# Eddy_Backplane.net
KiCad netlist of a schematic drawn in EAGLE
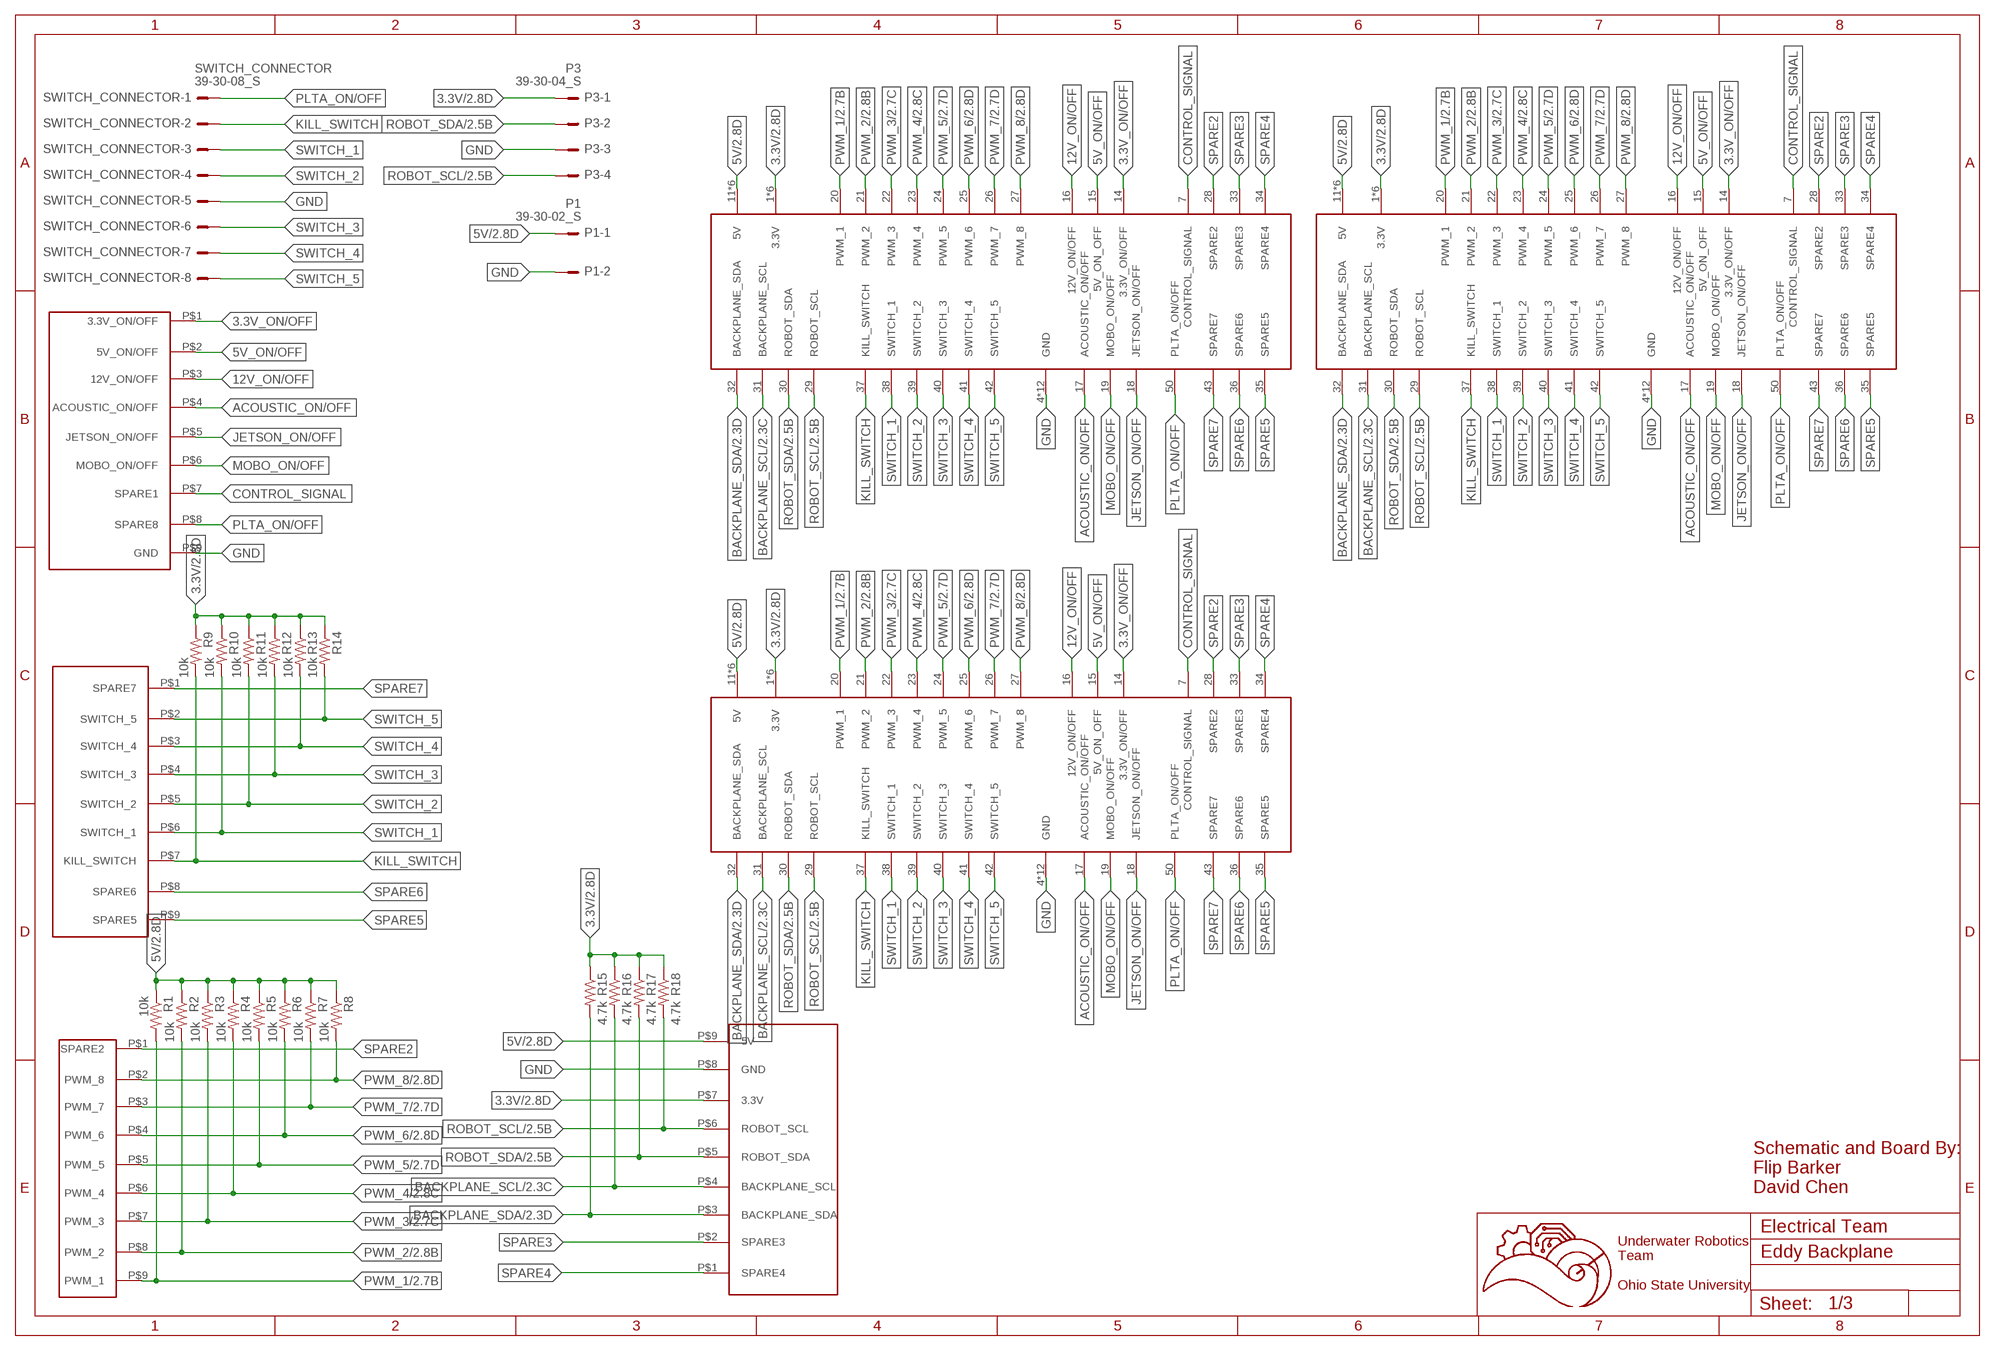
[diagram p0: schematic, sheet 1]
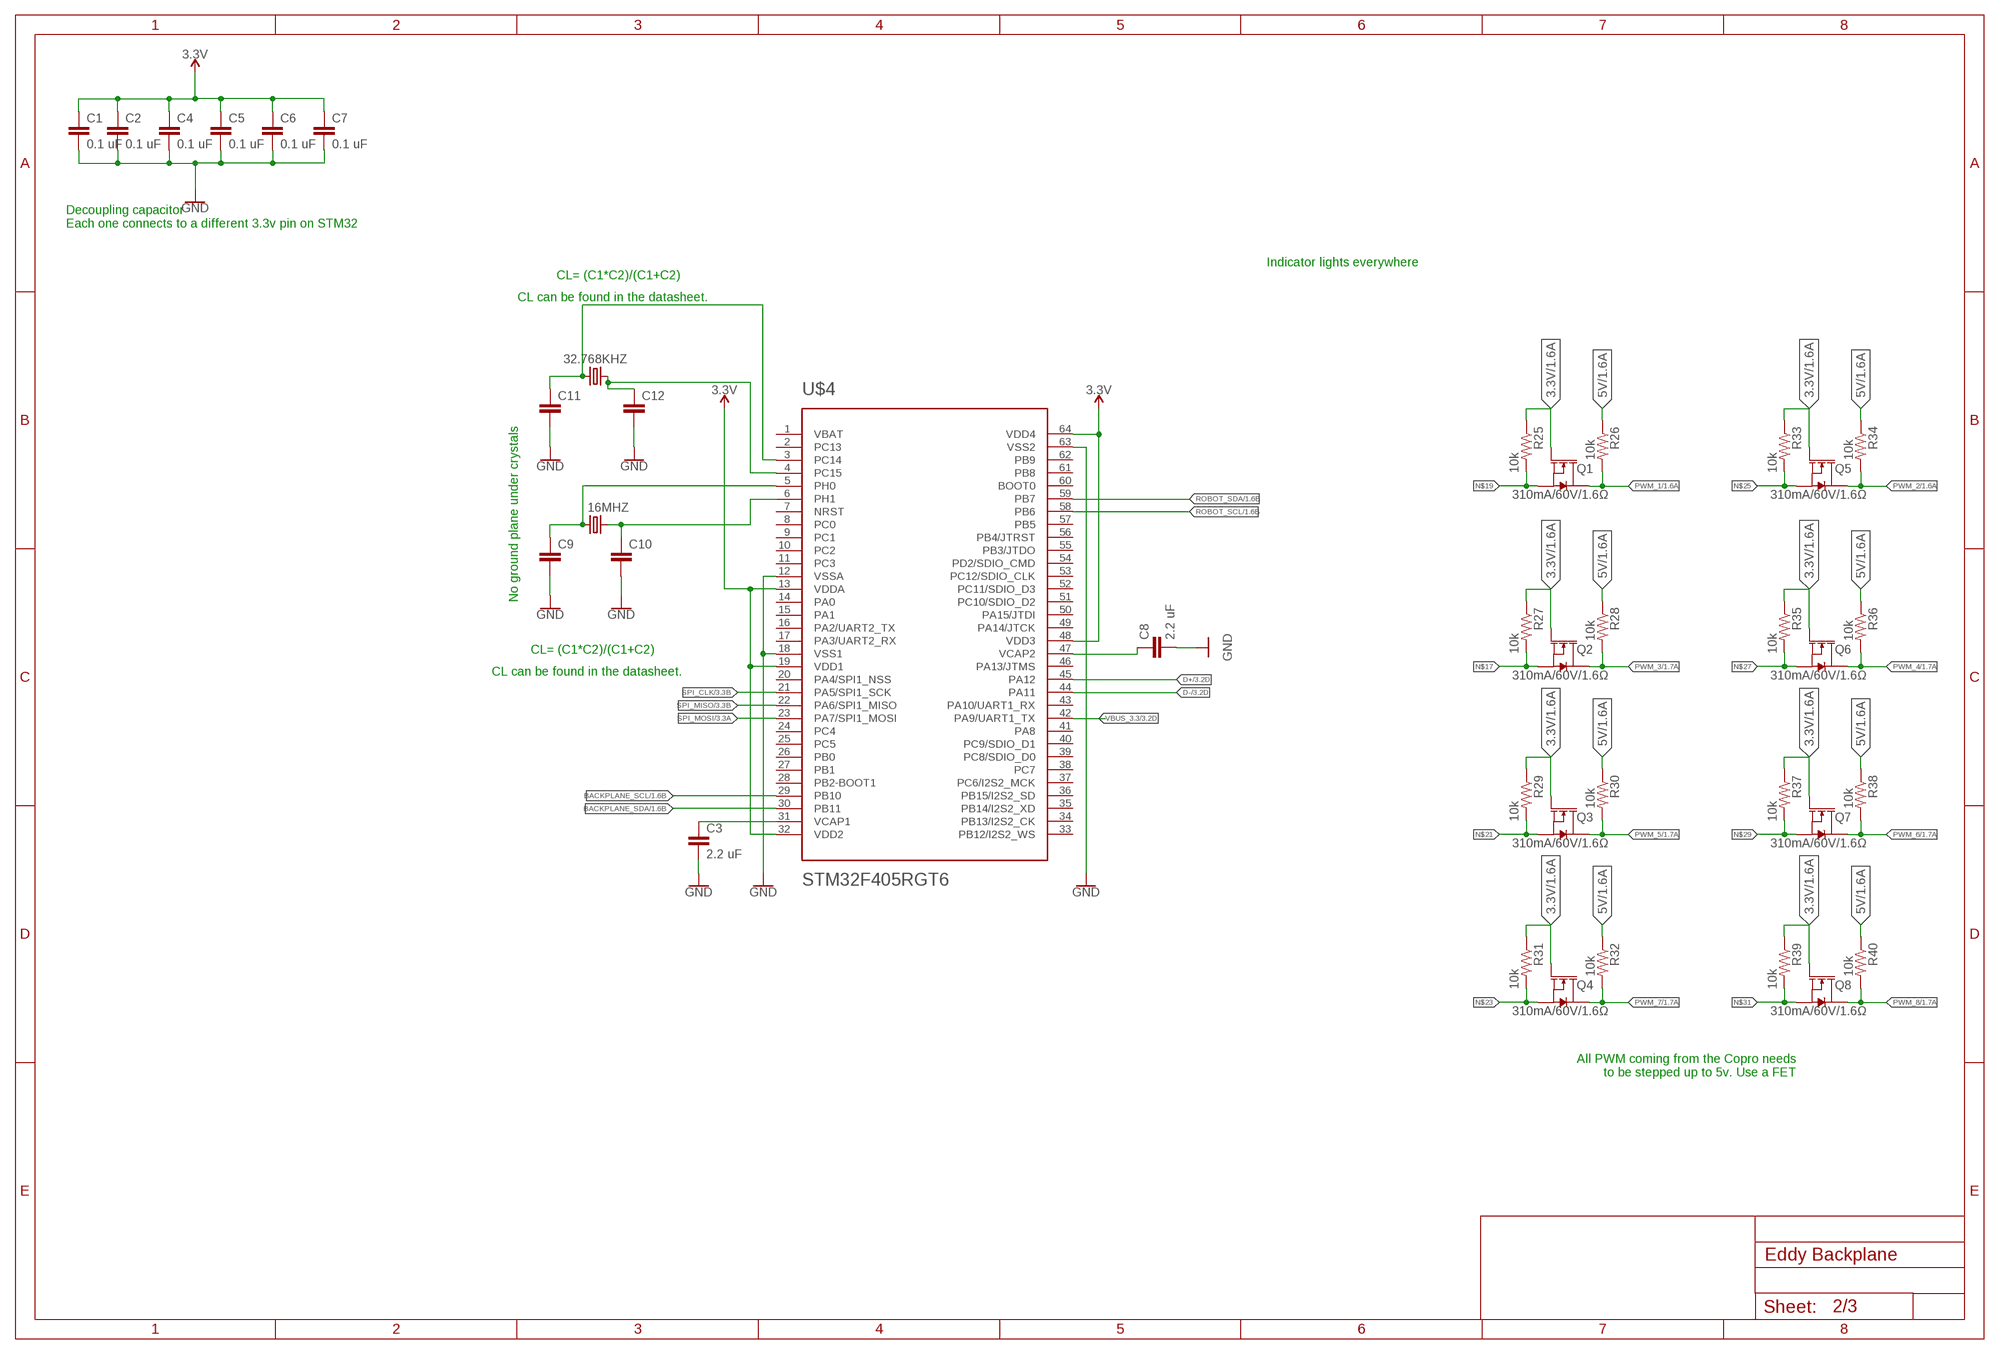
[diagram p1: schematic, sheet 2]
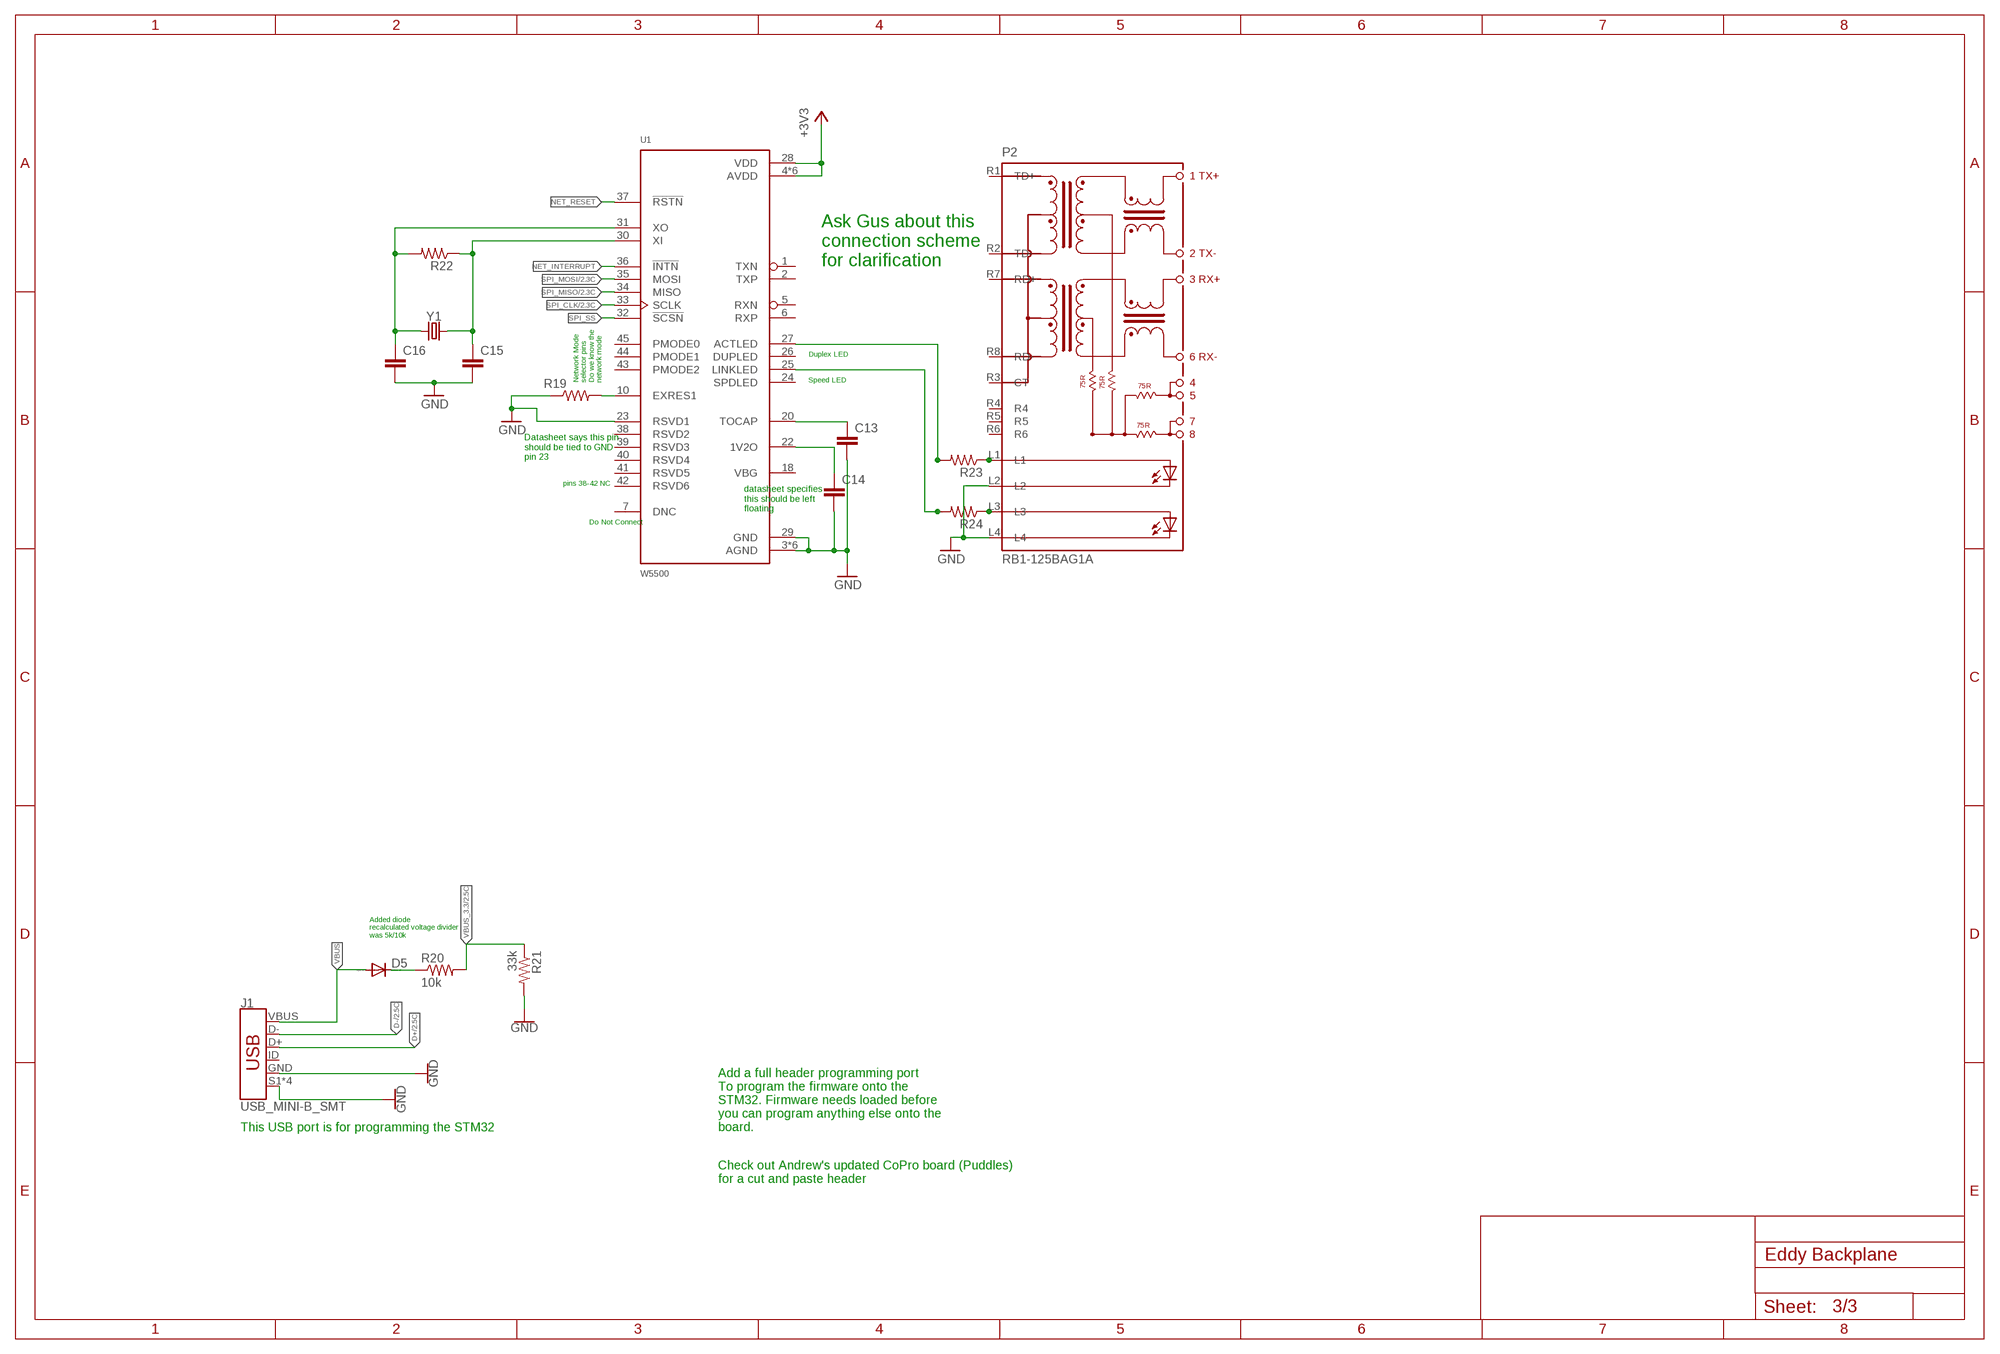
[diagram p2: schematic, sheet 3]

(export (version "E")
  (design (tool "Eeschema 10.0.6"))
  (components
    (comp (ref "C13")
      (value "C-EUC0603")
      (footprint "eagle-import:C0603")
      (libsource (lib "eagle-import") (part "C-EUC0603"))
    )
    (comp (ref "C14")
      (value "C-EUC0603")
      (footprint "eagle-import:C0603")
      (libsource (lib "eagle-import") (part "C-EUC0603"))
    )
    (comp (ref "C15")
      (value "C-EUC0603")
      (footprint "eagle-import:C0603")
      (libsource (lib "eagle-import") (part "C-EUC0603"))
    )
    (comp (ref "C16")
      (value "C-EUC0603")
      (footprint "eagle-import:C0603")
      (libsource (lib "eagle-import") (part "C-EUC0603"))
    )
    (comp (ref "D5")
      (value "DIODE-SMB")
      (footprint "eagle-import:SMB")
      (libsource (lib "eagle-import") (part "DIODE-SMB"))
    )
    (comp (ref "J1")
      (value "USB_MINI-B_SMT")
      (footprint "eagle-import:USB-MINIB")
      (libsource (lib "eagle-import") (part "USB_MINI-B_SMT"))
    )
    (comp (ref "P2")
      (value "RB1-125BAG1A")
      (footprint "eagle-import:WIZNET_RB1-125BAG1A")
      (fields (field (name "MF") "WIZnet"))
      (libsource (lib "eagle-import") (part "RB1-125BAG1A"))
    )
    (comp (ref "R19")
      (value "R-US_R0603")
      (footprint "eagle-import:R0603")
      (libsource (lib "eagle-import") (part "R-US_R0603"))
    )
    (comp (ref "R20")
      (value "10k")
      (footprint "eagle-import:R0603")
      (libsource (lib "eagle-import") (part "R-US_R0603"))
    )
    (comp (ref "R21")
      (value "33k")
      (footprint "eagle-import:R0603")
      (libsource (lib "eagle-import") (part "R-US_R0603"))
    )
    (comp (ref "R22")
      (value "R-US_R0603")
      (footprint "eagle-import:R0603")
      (libsource (lib "eagle-import") (part "R-US_R0603"))
    )
    (comp (ref "R23")
      (value "R-US_R0603")
      (footprint "eagle-import:R0603")
      (libsource (lib "eagle-import") (part "R-US_R0603"))
    )
    (comp (ref "R24")
      (value "R-US_R0603")
      (footprint "eagle-import:R0603")
      (libsource (lib "eagle-import") (part "R-US_R0603"))
    )
    (comp (ref "U1")
      (value "W5500")
      (footprint "eagle-import:QFP50P900X900X160-48N")
      (fields (field (name "MF") "WIZnet"))
      (libsource (lib "eagle-import") (part "W5500"))
    )
    (comp (ref "Y1")
      (value "CRYSTALPTH-HC49US")
      (footprint "eagle-import:HC49US")
      (libsource (lib "eagle-import") (part "SparkFun-Clocks_511_CRYSTALPTH-HC49US"))
    )
    (comp (ref "P1")
      (value "39-30-02_S")
      (footprint "eagle-import:39-30-_02_")
      (libsource (lib "eagle-import") (part "39-30-?02?_S"))
    )
    (comp (ref "P3")
      (value "39-30-04_S")
      (footprint "eagle-import:39-30-_04_")
      (libsource (lib "eagle-import") (part "39-30-?04?_S"))
    )
    (comp (ref "PWR_ON")
      (value "929870-01-09_3")
      (footprint "eagle-import:929852-01-09_1ROW")
      (libsource (lib "eagle-import") (part "929870-01-09_3"))
    )
    (comp (ref "R1")
      (value "10k")
      (footprint "eagle-import:R0603")
      (libsource (lib "eagle-import") (part "R-US_R0603"))
    )
    (comp (ref "R2")
      (value "10k")
      (footprint "eagle-import:R0603")
      (libsource (lib "eagle-import") (part "R-US_R0603"))
    )
    (comp (ref "R3")
      (value "10k")
      (footprint "eagle-import:R0603")
      (libsource (lib "eagle-import") (part "R-US_R0603"))
    )
    (comp (ref "R4")
      (value "10k")
      (footprint "eagle-import:R0603")
      (libsource (lib "eagle-import") (part "R-US_R0603"))
    )
    (comp (ref "R5")
      (value "10k")
      (footprint "eagle-import:R0603")
      (libsource (lib "eagle-import") (part "R-US_R0603"))
    )
    (comp (ref "R6")
      (value "10k")
      (footprint "eagle-import:R0603")
      (libsource (lib "eagle-import") (part "R-US_R0603"))
    )
    (comp (ref "R7")
      (value "10k")
      (footprint "eagle-import:R0603")
      (libsource (lib "eagle-import") (part "R-US_R0603"))
    )
    (comp (ref "R8")
      (value "10k")
      (footprint "eagle-import:R0603")
      (libsource (lib "eagle-import") (part "R-US_R0603"))
    )
    (comp (ref "R9")
      (value "10k")
      (footprint "eagle-import:R0603")
      (libsource (lib "eagle-import") (part "R-US_R0603"))
    )
    (comp (ref "R10")
      (value "10k")
      (footprint "eagle-import:R0603")
      (libsource (lib "eagle-import") (part "R-US_R0603"))
    )
    (comp (ref "R11")
      (value "10k")
      (footprint "eagle-import:R0603")
      (libsource (lib "eagle-import") (part "R-US_R0603"))
    )
    (comp (ref "R12")
      (value "10k")
      (footprint "eagle-import:R0603")
      (libsource (lib "eagle-import") (part "R-US_R0603"))
    )
    (comp (ref "R13")
      (value "10k")
      (footprint "eagle-import:R0603")
      (libsource (lib "eagle-import") (part "R-US_R0603"))
    )
    (comp (ref "R14")
      (value "10k")
      (footprint "eagle-import:R0603")
      (libsource (lib "eagle-import") (part "R-US_R0603"))
    )
    (comp (ref "R15")
      (value "4.7k")
      (footprint "eagle-import:R0603")
      (libsource (lib "eagle-import") (part "R-US_R0603"))
    )
    (comp (ref "R16")
      (value "4.7k")
      (footprint "eagle-import:R0603")
      (libsource (lib "eagle-import") (part "R-US_R0603"))
    )
    (comp (ref "R17")
      (value "4.7k")
      (footprint "eagle-import:R0603")
      (libsource (lib "eagle-import") (part "R-US_R0603"))
    )
    (comp (ref "R18")
      (value "4.7k")
      (footprint "eagle-import:R0603")
      (libsource (lib "eagle-import") (part "R-US_R0603"))
    )
    (comp (ref "SWITCH_CONN")
      (value "929870-01-09_1")
      (footprint "eagle-import:929852-01-09_1ROW")
      (libsource (lib "eagle-import") (part "929870-01-09_1"))
    )
    (comp (ref "SWITCH_CONNECTOR")
      (value "39-30-08_S")
      (footprint "eagle-import:39-30-_08_")
      (libsource (lib "eagle-import") (part "39-30-?08?_S"))
    )
    (comp (ref "U$1")
      (value "5530843-FEMALE")
      (footprint "eagle-import:5530843-6-BACKPLANEMATE")
      (libsource (lib "eagle-import") (part "5530843-FEMALE"))
    )
    (comp (ref "U$2")
      (value "5530843-FEMALE")
      (footprint "eagle-import:5530843-6-BACKPLANEMATE")
      (libsource (lib "eagle-import") (part "5530843-FEMALE"))
    )
    (comp (ref "U$3")
      (value "5530843-FEMALE")
      (footprint "eagle-import:5530843-6-BACKPLANEMATE")
      (libsource (lib "eagle-import") (part "5530843-FEMALE"))
    )
    (comp (ref "U$6")
      (value "929870-01-09_2")
      (footprint "eagle-import:929852-01-09_1ROW")
      (libsource (lib "eagle-import") (part "929870-01-09_2"))
    )
    (comp (ref "U$8")
      (value "929870-01-09_4")
      (footprint "eagle-import:929852-01-09_1ROW")
      (libsource (lib "eagle-import") (part "929870-01-09_4"))
    )
    (comp (ref "16MHZ")
      (value "CRYSTALPTH-HC49US")
      (footprint "eagle-import:HC49US")
      (libsource (lib "eagle-import") (part "CRYSTALPTH-HC49US"))
    )
    (comp (ref "32.768KHZ")
      (value "CRYSTALPTH-HC49US")
      (footprint "eagle-import:HC49US")
      (libsource (lib "eagle-import") (part "CRYSTALPTH-HC49US"))
    )
    (comp (ref "C1")
      (value "0.1 uF")
      (footprint "eagle-import:C0603")
      (libsource (lib "eagle-import") (part "C-EUC0603"))
    )
    (comp (ref "C2")
      (value "0.1 uF")
      (footprint "eagle-import:C0603")
      (libsource (lib "eagle-import") (part "C-EUC0603"))
    )
    (comp (ref "C3")
      (value "2.2 uF")
      (footprint "eagle-import:C0603")
      (libsource (lib "eagle-import") (part "C-EUC0603"))
    )
    (comp (ref "C4")
      (value "0.1 uF")
      (footprint "eagle-import:C0603")
      (libsource (lib "eagle-import") (part "C-EUC0603"))
    )
    (comp (ref "C5")
      (value "0.1 uF")
      (footprint "eagle-import:C0603")
      (libsource (lib "eagle-import") (part "C-EUC0603"))
    )
    (comp (ref "C6")
      (value "0.1 uF")
      (footprint "eagle-import:C0603")
      (libsource (lib "eagle-import") (part "C-EUC0603"))
    )
    (comp (ref "C7")
      (value "0.1 uF")
      (footprint "eagle-import:C0603")
      (libsource (lib "eagle-import") (part "C-EUC0603"))
    )
    (comp (ref "C8")
      (value "2.2 uF")
      (footprint "eagle-import:C0603")
      (libsource (lib "eagle-import") (part "C-EUC0603"))
    )
    (comp (ref "C9")
      (value "C-EUC0603")
      (footprint "eagle-import:C0603")
      (libsource (lib "eagle-import") (part "C-EUC0603"))
    )
    (comp (ref "C10")
      (value "C-EUC0603")
      (footprint "eagle-import:C0603")
      (libsource (lib "eagle-import") (part "C-EUC0603"))
    )
    (comp (ref "C11")
      (value "C-EUC0603")
      (footprint "eagle-import:C0603")
      (libsource (lib "eagle-import") (part "C-EUC0603"))
    )
    (comp (ref "C12")
      (value "C-EUC0603")
      (footprint "eagle-import:C0603")
      (libsource (lib "eagle-import") (part "C-EUC0603"))
    )
    (comp (ref "Q1")
      (value "310mA/60V/1.6Ω")
      (footprint "eagle-import:SOT323")
      (libsource (lib "eagle-import") (part "MOSFET-NCH-2N7002PW"))
    )
    (comp (ref "Q2")
      (value "310mA/60V/1.6Ω")
      (footprint "eagle-import:SOT323")
      (libsource (lib "eagle-import") (part "MOSFET-NCH-2N7002PW"))
    )
    (comp (ref "Q3")
      (value "310mA/60V/1.6Ω")
      (footprint "eagle-import:SOT323")
      (libsource (lib "eagle-import") (part "MOSFET-NCH-2N7002PW"))
    )
    (comp (ref "Q4")
      (value "310mA/60V/1.6Ω")
      (footprint "eagle-import:SOT323")
      (libsource (lib "eagle-import") (part "MOSFET-NCH-2N7002PW"))
    )
    (comp (ref "Q5")
      (value "310mA/60V/1.6Ω")
      (footprint "eagle-import:SOT323")
      (libsource (lib "eagle-import") (part "MOSFET-NCH-2N7002PW"))
    )
    (comp (ref "Q6")
      (value "310mA/60V/1.6Ω")
      (footprint "eagle-import:SOT323")
      (libsource (lib "eagle-import") (part "MOSFET-NCH-2N7002PW"))
    )
    (comp (ref "Q7")
      (value "310mA/60V/1.6Ω")
      (footprint "eagle-import:SOT323")
      (libsource (lib "eagle-import") (part "MOSFET-NCH-2N7002PW"))
    )
    (comp (ref "Q8")
      (value "310mA/60V/1.6Ω")
      (footprint "eagle-import:SOT323")
      (libsource (lib "eagle-import") (part "MOSFET-NCH-2N7002PW"))
    )
    (comp (ref "R25")
      (value "10k")
      (footprint "eagle-import:R0603")
      (libsource (lib "eagle-import") (part "R-US_R0603"))
    )
    (comp (ref "R26")
      (value "10k")
      (footprint "eagle-import:R0603")
      (libsource (lib "eagle-import") (part "R-US_R0603"))
    )
    (comp (ref "R27")
      (value "10k")
      (footprint "eagle-import:R0603")
      (libsource (lib "eagle-import") (part "R-US_R0603"))
    )
    (comp (ref "R28")
      (value "10k")
      (footprint "eagle-import:R0603")
      (libsource (lib "eagle-import") (part "R-US_R0603"))
    )
    (comp (ref "R29")
      (value "10k")
      (footprint "eagle-import:R0603")
      (libsource (lib "eagle-import") (part "R-US_R0603"))
    )
    (comp (ref "R30")
      (value "10k")
      (footprint "eagle-import:R0603")
      (libsource (lib "eagle-import") (part "R-US_R0603"))
    )
    (comp (ref "R31")
      (value "10k")
      (footprint "eagle-import:R0603")
      (libsource (lib "eagle-import") (part "R-US_R0603"))
    )
    (comp (ref "R32")
      (value "10k")
      (footprint "eagle-import:R0603")
      (libsource (lib "eagle-import") (part "R-US_R0603"))
    )
    (comp (ref "R33")
      (value "10k")
      (footprint "eagle-import:R0603")
      (libsource (lib "eagle-import") (part "R-US_R0603"))
    )
    (comp (ref "R34")
      (value "10k")
      (footprint "eagle-import:R0603")
      (libsource (lib "eagle-import") (part "R-US_R0603"))
    )
    (comp (ref "R35")
      (value "10k")
      (footprint "eagle-import:R0603")
      (libsource (lib "eagle-import") (part "R-US_R0603"))
    )
    (comp (ref "R36")
      (value "10k")
      (footprint "eagle-import:R0603")
      (libsource (lib "eagle-import") (part "R-US_R0603"))
    )
    (comp (ref "R37")
      (value "10k")
      (footprint "eagle-import:R0603")
      (libsource (lib "eagle-import") (part "R-US_R0603"))
    )
    (comp (ref "R38")
      (value "10k")
      (footprint "eagle-import:R0603")
      (libsource (lib "eagle-import") (part "R-US_R0603"))
    )
    (comp (ref "R39")
      (value "10k")
      (footprint "eagle-import:R0603")
      (libsource (lib "eagle-import") (part "R-US_R0603"))
    )
    (comp (ref "R40")
      (value "10k")
      (footprint "eagle-import:R0603")
      (libsource (lib "eagle-import") (part "R-US_R0603"))
    )
    (comp (ref "U$4")
      (value "STM32F405RGT6")
      (footprint "eagle-import:TQFP64")
      (libsource (lib "eagle-import") (part "STM32F405RG"))
    )
  )
  (nets
    (net (code "1") (name "+3V3") (class "Default")
      (node (ref "U1") (pin "11") (pinfunction "AVDD_11") (pintype "power_in"))
      (node (ref "U1") (pin "15") (pinfunction "AVDD_15") (pintype "power_in"))
      (node (ref "U1") (pin "17") (pinfunction "AVDD_17") (pintype "power_in"))
      (node (ref "U1") (pin "21") (pinfunction "AVDD_21") (pintype "power_in"))
      (node (ref "U1") (pin "28") (pinfunction "VDD_28") (pintype "power_in"))
      (node (ref "U1") (pin "4") (pinfunction "AVDD_4") (pintype "power_in"))
      (node (ref "U1") (pin "8") (pinfunction "AVDD_8") (pintype "power_in"))
    )
    (net (code "2") (name "3.3V") (class "Default")
      (node (ref "C1") (pin "1") (pinfunction "1_1") (pintype "passive"))
      (node (ref "C2") (pin "1") (pinfunction "1_1") (pintype "passive"))
      (node (ref "C4") (pin "1") (pinfunction "1_1") (pintype "passive"))
      (node (ref "C5") (pin "1") (pinfunction "1_1") (pintype "passive"))
      (node (ref "C6") (pin "1") (pinfunction "1_1") (pintype "passive"))
      (node (ref "C7") (pin "1") (pinfunction "1_1") (pintype "passive"))
      (node (ref "P3") (pin "1") (pinfunction "P_1") (pintype "passive"))
      (node (ref "Q1") (pin "1") (pinfunction "G_1") (pintype "bidirectional"))
      (node (ref "Q2") (pin "1") (pinfunction "G_1") (pintype "bidirectional"))
      (node (ref "Q3") (pin "1") (pinfunction "G_1") (pintype "bidirectional"))
      (node (ref "Q4") (pin "1") (pinfunction "G_1") (pintype "bidirectional"))
      (node (ref "Q5") (pin "1") (pinfunction "G_1") (pintype "bidirectional"))
      (node (ref "Q6") (pin "1") (pinfunction "G_1") (pintype "bidirectional"))
      (node (ref "Q7") (pin "1") (pinfunction "G_1") (pintype "bidirectional"))
      (node (ref "Q8") (pin "1") (pinfunction "G_1") (pintype "bidirectional"))
      (node (ref "R10") (pin "1") (pinfunction "1_1") (pintype "passive"))
      (node (ref "R11") (pin "1") (pinfunction "1_1") (pintype "passive"))
      (node (ref "R12") (pin "1") (pinfunction "1_1") (pintype "passive"))
      (node (ref "R13") (pin "1") (pinfunction "1_1") (pintype "passive"))
      (node (ref "R14") (pin "1") (pinfunction "1_1") (pintype "passive"))
      (node (ref "R15") (pin "1") (pinfunction "1_1") (pintype "passive"))
      (node (ref "R16") (pin "1") (pinfunction "1_1") (pintype "passive"))
      (node (ref "R17") (pin "1") (pinfunction "1_1") (pintype "passive"))
      (node (ref "R18") (pin "1") (pinfunction "1_1") (pintype "passive"))
      (node (ref "R25") (pin "1") (pinfunction "1_1") (pintype "passive"))
      (node (ref "R27") (pin "1") (pinfunction "1_1") (pintype "passive"))
      (node (ref "R29") (pin "1") (pinfunction "1_1") (pintype "passive"))
      (node (ref "R31") (pin "1") (pinfunction "1_1") (pintype "passive"))
      (node (ref "R33") (pin "1") (pinfunction "1_1") (pintype "passive"))
      (node (ref "R35") (pin "1") (pinfunction "1_1") (pintype "passive"))
      (node (ref "R37") (pin "1") (pinfunction "1_1") (pintype "passive"))
      (node (ref "R39") (pin "1") (pinfunction "1_1") (pintype "passive"))
      (node (ref "R9") (pin "1") (pinfunction "1_1") (pintype "passive"))
      (node (ref "U$1") (pin "1") (pinfunction "3.3V_1") (pintype "bidirectional"))
      (node (ref "U$1") (pin "2") (pinfunction "3.3V_2") (pintype "bidirectional"))
      (node (ref "U$1") (pin "3") (pinfunction "3.3V_3") (pintype "bidirectional"))
      (node (ref "U$1") (pin "54") (pinfunction "3.3V_54") (pintype "bidirectional"))
      (node (ref "U$1") (pin "55") (pinfunction "3.3V_55") (pintype "bidirectional"))
      (node (ref "U$1") (pin "56") (pinfunction "3.3V_56") (pintype "bidirectional"))
      (node (ref "U$2") (pin "1") (pinfunction "3.3V_1") (pintype "bidirectional"))
      (node (ref "U$2") (pin "2") (pinfunction "3.3V_2") (pintype "bidirectional"))
      (node (ref "U$2") (pin "3") (pinfunction "3.3V_3") (pintype "bidirectional"))
      (node (ref "U$2") (pin "54") (pinfunction "3.3V_54") (pintype "bidirectional"))
      (node (ref "U$2") (pin "55") (pinfunction "3.3V_55") (pintype "bidirectional"))
      (node (ref "U$2") (pin "56") (pinfunction "3.3V_56") (pintype "bidirectional"))
      (node (ref "U$3") (pin "1") (pinfunction "3.3V_1") (pintype "bidirectional"))
      (node (ref "U$3") (pin "2") (pinfunction "3.3V_2") (pintype "bidirectional"))
      (node (ref "U$3") (pin "3") (pinfunction "3.3V_3") (pintype "bidirectional"))
      (node (ref "U$3") (pin "54") (pinfunction "3.3V_54") (pintype "bidirectional"))
      (node (ref "U$3") (pin "55") (pinfunction "3.3V_55") (pintype "bidirectional"))
      (node (ref "U$3") (pin "56") (pinfunction "3.3V_56") (pintype "bidirectional"))
      (node (ref "U$4") (pin "13") (pinfunction "VDDA_13") (pintype "bidirectional"))
      (node (ref "U$4") (pin "19") (pinfunction "VDD1_19") (pintype "bidirectional"))
      (node (ref "U$4") (pin "32") (pinfunction "VDD2_32") (pintype "bidirectional"))
      (node (ref "U$4") (pin "48") (pinfunction "VDD3_48") (pintype "bidirectional"))
      (node (ref "U$4") (pin "64") (pinfunction "VDD4_64") (pintype "bidirectional"))
      (node (ref "U$8") (pin "P$7") (pinfunction "3.3V_P$7") (pintype "bidirectional"))
    )
    (net (code "3") (name "3.3V_ON{slash}OFF") (class "Default")
      (node (ref "PWR_ON") (pin "P$1") (pinfunction "3.3V_ON/OFF_P$1") (pintype "bidirectional"))
      (node (ref "U$1") (pin "14") (pinfunction "3.3V_ON/OFF_14") (pintype "bidirectional"))
      (node (ref "U$2") (pin "14") (pinfunction "3.3V_ON/OFF_14") (pintype "bidirectional"))
      (node (ref "U$3") (pin "14") (pinfunction "3.3V_ON/OFF_14") (pintype "bidirectional"))
    )
    (net (code "4") (name "5V") (class "Default")
      (node (ref "P1") (pin "1") (pinfunction "P_1") (pintype "passive"))
      (node (ref "R1") (pin "1") (pinfunction "1_1") (pintype "passive"))
      (node (ref "R2") (pin "1") (pinfunction "1_1") (pintype "passive"))
      (node (ref "R26") (pin "1") (pinfunction "1_1") (pintype "passive"))
      (node (ref "R28") (pin "1") (pinfunction "1_1") (pintype "passive"))
      (node (ref "R3") (pin "1") (pinfunction "1_1") (pintype "passive"))
      (node (ref "R30") (pin "1") (pinfunction "1_1") (pintype "passive"))
      (node (ref "R32") (pin "1") (pinfunction "1_1") (pintype "passive"))
      (node (ref "R34") (pin "1") (pinfunction "1_1") (pintype "passive"))
      (node (ref "R36") (pin "1") (pinfunction "1_1") (pintype "passive"))
      (node (ref "R38") (pin "1") (pinfunction "1_1") (pintype "passive"))
      (node (ref "R4") (pin "1") (pinfunction "1_1") (pintype "passive"))
      (node (ref "R40") (pin "1") (pinfunction "1_1") (pintype "passive"))
      (node (ref "R5") (pin "1") (pinfunction "1_1") (pintype "passive"))
      (node (ref "R6") (pin "1") (pinfunction "1_1") (pintype "passive"))
      (node (ref "R7") (pin "1") (pinfunction "1_1") (pintype "passive"))
      (node (ref "R8") (pin "1") (pinfunction "1_1") (pintype "passive"))
      (node (ref "U$1") (pin "11") (pinfunction "5V_11") (pintype "bidirectional"))
      (node (ref "U$1") (pin "12") (pinfunction "5V_12") (pintype "bidirectional"))
      (node (ref "U$1") (pin "13") (pinfunction "5V_13") (pintype "bidirectional"))
      (node (ref "U$1") (pin "44") (pinfunction "5V_44") (pintype "bidirectional"))
      (node (ref "U$1") (pin "45") (pinfunction "5V_45") (pintype "bidirectional"))
      (node (ref "U$1") (pin "46") (pinfunction "5V_46") (pintype "bidirectional"))
      (node (ref "U$2") (pin "11") (pinfunction "5V_11") (pintype "bidirectional"))
      (node (ref "U$2") (pin "12") (pinfunction "5V_12") (pintype "bidirectional"))
      (node (ref "U$2") (pin "13") (pinfunction "5V_13") (pintype "bidirectional"))
      (node (ref "U$2") (pin "44") (pinfunction "5V_44") (pintype "bidirectional"))
      (node (ref "U$2") (pin "45") (pinfunction "5V_45") (pintype "bidirectional"))
      (node (ref "U$2") (pin "46") (pinfunction "5V_46") (pintype "bidirectional"))
      (node (ref "U$3") (pin "11") (pinfunction "5V_11") (pintype "bidirectional"))
      (node (ref "U$3") (pin "12") (pinfunction "5V_12") (pintype "bidirectional"))
      (node (ref "U$3") (pin "13") (pinfunction "5V_13") (pintype "bidirectional"))
      (node (ref "U$3") (pin "44") (pinfunction "5V_44") (pintype "bidirectional"))
      (node (ref "U$3") (pin "45") (pinfunction "5V_45") (pintype "bidirectional"))
      (node (ref "U$3") (pin "46") (pinfunction "5V_46") (pintype "bidirectional"))
      (node (ref "U$8") (pin "P$9") (pinfunction "5V_P$9") (pintype "bidirectional"))
    )
    (net (code "5") (name "5V_ON{slash}OFF") (class "Default")
      (node (ref "PWR_ON") (pin "P$2") (pinfunction "5V_ON/OFF_P$2") (pintype "bidirectional"))
      (node (ref "U$1") (pin "15") (pinfunction "5V_ON_OFF_15") (pintype "bidirectional"))
      (node (ref "U$2") (pin "15") (pinfunction "5V_ON_OFF_15") (pintype "bidirectional"))
      (node (ref "U$3") (pin "15") (pinfunction "5V_ON_OFF_15") (pintype "bidirectional"))
    )
    (net (code "6") (name "12V_ON{slash}OFF") (class "Default")
      (node (ref "PWR_ON") (pin "P$3") (pinfunction "12V_ON/OFF_P$3") (pintype "bidirectional"))
      (node (ref "U$1") (pin "16") (pinfunction "12V_ON/OFF_16") (pintype "bidirectional"))
      (node (ref "U$2") (pin "16") (pinfunction "12V_ON/OFF_16") (pintype "bidirectional"))
      (node (ref "U$3") (pin "16") (pinfunction "12V_ON/OFF_16") (pintype "bidirectional"))
    )
    (net (code "7") (name "ACOUSTIC_ON{slash}OFF") (class "Default")
      (node (ref "PWR_ON") (pin "P$4") (pinfunction "ACOUSTIC_ON/OFF_P$4") (pintype "bidirectional"))
      (node (ref "U$1") (pin "17") (pinfunction "ACOUSTIC_ON/OFF_17") (pintype "bidirectional"))
      (node (ref "U$2") (pin "17") (pinfunction "ACOUSTIC_ON/OFF_17") (pintype "bidirectional"))
      (node (ref "U$3") (pin "17") (pinfunction "ACOUSTIC_ON/OFF_17") (pintype "bidirectional"))
    )
    (net (code "8") (name "BACKPLANE_SCL") (class "Default")
      (node (ref "R16") (pin "2") (pinfunction "2_2") (pintype "passive"))
      (node (ref "U$1") (pin "31") (pinfunction "BACKPLANE_SCL_31") (pintype "bidirectional"))
      (node (ref "U$2") (pin "31") (pinfunction "BACKPLANE_SCL_31") (pintype "bidirectional"))
      (node (ref "U$3") (pin "31") (pinfunction "BACKPLANE_SCL_31") (pintype "bidirectional"))
      (node (ref "U$4") (pin "29") (pinfunction "PB10_29") (pintype "bidirectional"))
      (node (ref "U$8") (pin "P$4") (pinfunction "BACKPLANE_SCL_P$4") (pintype "bidirectional"))
    )
    (net (code "9") (name "BACKPLANE_SDA") (class "Default")
      (node (ref "R15") (pin "2") (pinfunction "2_2") (pintype "passive"))
      (node (ref "U$1") (pin "32") (pinfunction "BACKPLANE_SDA_32") (pintype "bidirectional"))
      (node (ref "U$2") (pin "32") (pinfunction "BACKPLANE_SDA_32") (pintype "bidirectional"))
      (node (ref "U$3") (pin "32") (pinfunction "BACKPLANE_SDA_32") (pintype "bidirectional"))
      (node (ref "U$4") (pin "30") (pinfunction "PB11_30") (pintype "bidirectional"))
      (node (ref "U$8") (pin "P$3") (pinfunction "BACKPLANE_SDA_P$3") (pintype "bidirectional"))
    )
    (net (code "10") (name "CONTROL_SIGNAL") (class "Default")
      (node (ref "PWR_ON") (pin "P$7") (pinfunction "SPARE1_P$7") (pintype "bidirectional"))
      (node (ref "U$1") (pin "7") (pinfunction "CONTROL_SIGNAL_7") (pintype "bidirectional"))
      (node (ref "U$2") (pin "7") (pinfunction "CONTROL_SIGNAL_7") (pintype "bidirectional"))
      (node (ref "U$3") (pin "7") (pinfunction "CONTROL_SIGNAL_7") (pintype "bidirectional"))
    )
    (net (code "11") (name "D+") (class "Default")
      (node (ref "J1") (pin "D+") (pinfunction "D+_D+") (pintype "bidirectional"))
      (node (ref "U$4") (pin "45") (pinfunction "PA12_45") (pintype "bidirectional"))
    )
    (net (code "12") (name "D-") (class "Default")
      (node (ref "J1") (pin "D-") (pinfunction "D-_D-") (pintype "bidirectional"))
      (node (ref "U$4") (pin "44") (pinfunction "PA11_44") (pintype "bidirectional"))
    )
    (net (code "13") (name "GND") (class "Default")
      (node (ref "C1") (pin "2") (pinfunction "2_2") (pintype "passive"))
      (node (ref "C10") (pin "2") (pinfunction "2_2") (pintype "passive"))
      (node (ref "C11") (pin "2") (pinfunction "2_2") (pintype "passive"))
      (node (ref "C12") (pin "2") (pinfunction "2_2") (pintype "passive"))
      (node (ref "C13") (pin "2") (pinfunction "2_2") (pintype "passive"))
      (node (ref "C14") (pin "2") (pinfunction "2_2") (pintype "passive"))
      (node (ref "C15") (pin "2") (pinfunction "2_2") (pintype "passive"))
      (node (ref "C16") (pin "2") (pinfunction "2_2") (pintype "passive"))
      (node (ref "C2") (pin "2") (pinfunction "2_2") (pintype "passive"))
      (node (ref "C3") (pin "2") (pinfunction "2_2") (pintype "passive"))
      (node (ref "C4") (pin "2") (pinfunction "2_2") (pintype "passive"))
      (node (ref "C5") (pin "2") (pinfunction "2_2") (pintype "passive"))
      (node (ref "C6") (pin "2") (pinfunction "2_2") (pintype "passive"))
      (node (ref "C7") (pin "2") (pinfunction "2_2") (pintype "passive"))
      (node (ref "C8") (pin "2") (pinfunction "2_2") (pintype "passive"))
      (node (ref "C9") (pin "2") (pinfunction "2_2") (pintype "passive"))
      (node (ref "J1") (pin "GND") (pinfunction "GND_GND") (pintype "power_in"))
      (node (ref "J1") (pin "S1") (pinfunction "SHIELD_S1") (pintype "bidirectional"))
      (node (ref "J1") (pin "S2") (pinfunction "SHIELD_S2") (pintype "bidirectional"))
      (node (ref "J1") (pin "S3") (pinfunction "SHIELD_S3") (pintype "bidirectional"))
      (node (ref "J1") (pin "S4") (pinfunction "SHIELD_S4") (pintype "bidirectional"))
      (node (ref "P1") (pin "2") (pinfunction "P_2") (pintype "passive"))
      (node (ref "P2") (pin "L2") (pinfunction "L2_L2") (pintype "passive"))
      (node (ref "P2") (pin "L4") (pinfunction "L4_L4") (pintype "passive"))
      (node (ref "P3") (pin "3") (pinfunction "P_3") (pintype "passive"))
      (node (ref "PWR_ON") (pin "P$9") (pinfunction "GND_P$9") (pintype "bidirectional"))
      (node (ref "R19") (pin "1") (pinfunction "1_1") (pintype "passive"))
      (node (ref "R21") (pin "2") (pinfunction "2_2") (pintype "passive"))
      (node (ref "SWITCH_CONNECTOR") (pin "5") (pinfunction "P_5") (pintype "passive"))
      (node (ref "U$1") (pin "10") (pinfunction "GND_10") (pintype "bidirectional"))
      (node (ref "U$1") (pin "4") (pinfunction "GND_4") (pintype "bidirectional"))
      (node (ref "U$1") (pin "47") (pinfunction "GND_47") (pintype "bidirectional"))
      (node (ref "U$1") (pin "48") (pinfunction "GND_48") (pintype "bidirectional"))
      (node (ref "U$1") (pin "49") (pinfunction "GND_49") (pintype "bidirectional"))
      (node (ref "U$1") (pin "5") (pinfunction "GND_5") (pintype "bidirectional"))
      (node (ref "U$1") (pin "51") (pinfunction "GND_51") (pintype "bidirectional"))
      (node (ref "U$1") (pin "52") (pinfunction "GND_52") (pintype "bidirectional"))
      (node (ref "U$1") (pin "53") (pinfunction "GND_53") (pintype "bidirectional"))
      (node (ref "U$1") (pin "6") (pinfunction "GND_6") (pintype "bidirectional"))
      (node (ref "U$1") (pin "8") (pinfunction "GND_8") (pintype "bidirectional"))
      (node (ref "U$1") (pin "9") (pinfunction "GND_9") (pintype "bidirectional"))
      (node (ref "U$2") (pin "10") (pinfunction "GND_10") (pintype "bidirectional"))
      (node (ref "U$2") (pin "4") (pinfunction "GND_4") (pintype "bidirectional"))
      (node (ref "U$2") (pin "47") (pinfunction "GND_47") (pintype "bidirectional"))
      (node (ref "U$2") (pin "48") (pinfunction "GND_48") (pintype "bidirectional"))
      (node (ref "U$2") (pin "49") (pinfunction "GND_49") (pintype "bidirectional"))
      (node (ref "U$2") (pin "5") (pinfunction "GND_5") (pintype "bidirectional"))
      (node (ref "U$2") (pin "51") (pinfunction "GND_51") (pintype "bidirectional"))
      (node (ref "U$2") (pin "52") (pinfunction "GND_52") (pintype "bidirectional"))
      (node (ref "U$2") (pin "53") (pinfunction "GND_53") (pintype "bidirectional"))
      (node (ref "U$2") (pin "6") (pinfunction "GND_6") (pintype "bidirectional"))
      (node (ref "U$2") (pin "8") (pinfunction "GND_8") (pintype "bidirectional"))
      (node (ref "U$2") (pin "9") (pinfunction "GND_9") (pintype "bidirectional"))
      (node (ref "U$3") (pin "10") (pinfunction "GND_10") (pintype "bidirectional"))
      (node (ref "U$3") (pin "4") (pinfunction "GND_4") (pintype "bidirectional"))
      (node (ref "U$3") (pin "47") (pinfunction "GND_47") (pintype "bidirectional"))
      (node (ref "U$3") (pin "48") (pinfunction "GND_48") (pintype "bidirectional"))
      (node (ref "U$3") (pin "49") (pinfunction "GND_49") (pintype "bidirectional"))
      (node (ref "U$3") (pin "5") (pinfunction "GND_5") (pintype "bidirectional"))
      (node (ref "U$3") (pin "51") (pinfunction "GND_51") (pintype "bidirectional"))
      (node (ref "U$3") (pin "52") (pinfunction "GND_52") (pintype "bidirectional"))
      (node (ref "U$3") (pin "53") (pinfunction "GND_53") (pintype "bidirectional"))
      (node (ref "U$3") (pin "6") (pinfunction "GND_6") (pintype "bidirectional"))
      (node (ref "U$3") (pin "8") (pinfunction "GND_8") (pintype "bidirectional"))
      (node (ref "U$3") (pin "9") (pinfunction "GND_9") (pintype "bidirectional"))
      (node (ref "U$4") (pin "12") (pinfunction "VSSA_12") (pintype "bidirectional"))
      (node (ref "U$4") (pin "18") (pinfunction "VSS1_18") (pintype "bidirectional"))
      (node (ref "U$4") (pin "63") (pinfunction "VSS2_63") (pintype "bidirectional"))
      (node (ref "U$8") (pin "P$8") (pinfunction "GND_P$8") (pintype "bidirectional"))
      (node (ref "U1") (pin "14") (pinfunction "AGND_14") (pintype "power_in"))
      (node (ref "U1") (pin "16") (pinfunction "AGND_16") (pintype "power_in"))
      (node (ref "U1") (pin "19") (pinfunction "AGND_19") (pintype "power_in"))
      (node (ref "U1") (pin "23") (pinfunction "RSVD1_23") (pintype "input"))
      (node (ref "U1") (pin "29") (pinfunction "GND_29") (pintype "passive"))
      (node (ref "U1") (pin "3") (pinfunction "AGND_3") (pintype "power_in"))
      (node (ref "U1") (pin "48") (pinfunction "AGND_48") (pintype "power_in"))
      (node (ref "U1") (pin "9") (pinfunction "AGND_9") (pintype "power_in"))
    )
    (net (code "14") (name "JETSON_ON{slash}OFF") (class "Default")
      (node (ref "PWR_ON") (pin "P$5") (pinfunction "JETSON_ON/OFF_P$5") (pintype "bidirectional"))
      (node (ref "U$1") (pin "18") (pinfunction "JETSON_ON/OFF_18") (pintype "bidirectional"))
      (node (ref "U$2") (pin "18") (pinfunction "JETSON_ON/OFF_18") (pintype "bidirectional"))
      (node (ref "U$3") (pin "18") (pinfunction "JETSON_ON/OFF_18") (pintype "bidirectional"))
    )
    (net (code "15") (name "KILL_SWITCH") (class "Default")
      (node (ref "R9") (pin "2") (pinfunction "2_2") (pintype "passive"))
      (node (ref "SWITCH_CONN") (pin "P$7") (pinfunction "KILL_SWITCH_P$7") (pintype "bidirectional"))
      (node (ref "SWITCH_CONNECTOR") (pin "2") (pinfunction "P_2") (pintype "passive"))
      (node (ref "U$1") (pin "37") (pinfunction "KILL_SWITCH_37") (pintype "output"))
      (node (ref "U$2") (pin "37") (pinfunction "KILL_SWITCH_37") (pintype "output"))
      (node (ref "U$3") (pin "37") (pinfunction "KILL_SWITCH_37") (pintype "output"))
    )
    (net (code "16") (name "MOBO_ON{slash}OFF") (class "Default")
      (node (ref "PWR_ON") (pin "P$6") (pinfunction "MOBO_ON/OFF_P$6") (pintype "bidirectional"))
      (node (ref "U$1") (pin "19") (pinfunction "MOBO_ON/OFF_19") (pintype "bidirectional"))
      (node (ref "U$2") (pin "19") (pinfunction "MOBO_ON/OFF_19") (pintype "bidirectional"))
      (node (ref "U$3") (pin "19") (pinfunction "MOBO_ON/OFF_19") (pintype "bidirectional"))
    )
    (net (code "17") (name "N$17") (class "Default")
      (node (ref "Q2") (pin "2") (pinfunction "S_2") (pintype "bidirectional"))
      (node (ref "R27") (pin "2") (pinfunction "2_2") (pintype "passive"))
    )
    (net (code "18") (name "N$19") (class "Default")
      (node (ref "Q1") (pin "2") (pinfunction "S_2") (pintype "bidirectional"))
      (node (ref "R25") (pin "2") (pinfunction "2_2") (pintype "passive"))
    )
    (net (code "19") (name "N$21") (class "Default")
      (node (ref "Q3") (pin "2") (pinfunction "S_2") (pintype "bidirectional"))
      (node (ref "R29") (pin "2") (pinfunction "2_2") (pintype "passive"))
    )
    (net (code "20") (name "N$23") (class "Default")
      (node (ref "Q4") (pin "2") (pinfunction "S_2") (pintype "bidirectional"))
      (node (ref "R31") (pin "2") (pinfunction "2_2") (pintype "passive"))
    )
    (net (code "21") (name "N$25") (class "Default")
      (node (ref "Q5") (pin "2") (pinfunction "S_2") (pintype "bidirectional"))
      (node (ref "R33") (pin "2") (pinfunction "2_2") (pintype "passive"))
    )
    (net (code "22") (name "N$27") (class "Default")
      (node (ref "Q6") (pin "2") (pinfunction "S_2") (pintype "bidirectional"))
      (node (ref "R35") (pin "2") (pinfunction "2_2") (pintype "passive"))
    )
    (net (code "23") (name "N$29") (class "Default")
      (node (ref "Q7") (pin "2") (pinfunction "S_2") (pintype "bidirectional"))
      (node (ref "R37") (pin "2") (pinfunction "2_2") (pintype "passive"))
    )
    (net (code "24") (name "N$31") (class "Default")
      (node (ref "Q8") (pin "2") (pinfunction "S_2") (pintype "bidirectional"))
      (node (ref "R39") (pin "2") (pinfunction "2_2") (pintype "passive"))
    )
    (net (code "25") (name "NET_INTERRUPT") (class "Default")
      (node (ref "U1") (pin "36") (pinfunction "~{INTN}_36") (pintype "input"))
    )
    (net (code "26") (name "NET_RESET") (class "Default")
      (node (ref "U1") (pin "37") (pinfunction "~{RSTN}_37") (pintype "input"))
    )
    (net (code "27") (name "Net-(D5-PadC)") (class "Default")
      (node (ref "D5") (pin "C") (pinfunction "C_C") (pintype "passive"))
      (node (ref "R20") (pin "1") (pinfunction "1_1") (pintype "passive"))
    )
    (net (code "28") (name "Net-(P2-PadL1)") (class "Default")
      (node (ref "P2") (pin "L1") (pinfunction "L1_L1") (pintype "passive"))
      (node (ref "R23") (pin "1") (pinfunction "1_1") (pintype "passive"))
    )
    (net (code "29") (name "Net-(P2-PadL3)") (class "Default")
      (node (ref "P2") (pin "L3") (pinfunction "L3_L3") (pintype "passive"))
      (node (ref "R24") (pin "1") (pinfunction "1_1") (pintype "passive"))
    )
    (net (code "30") (name "Net-(U$4-PC14)") (class "Default")
      (node (ref "32.768KHZ") (pin "1") (pinfunction "1_1") (pintype "passive"))
      (node (ref "C11") (pin "1") (pinfunction "1_1") (pintype "passive"))
      (node (ref "U$4") (pin "3") (pinfunction "PC14_3") (pintype "bidirectional"))
    )
    (net (code "31") (name "Net-(U$4-PC15)") (class "Default")
      (node (ref "32.768KHZ") (pin "2") (pinfunction "2_2") (pintype "passive"))
      (node (ref "C12") (pin "1") (pinfunction "1_1") (pintype "passive"))
      (node (ref "U$4") (pin "4") (pinfunction "PC15_4") (pintype "bidirectional"))
    )
    (net (code "32") (name "Net-(U$4-PH0)") (class "Default")
      (node (ref "16MHZ") (pin "1") (pinfunction "1_1") (pintype "passive"))
      (node (ref "C9") (pin "1") (pinfunction "1_1") (pintype "passive"))
      (node (ref "U$4") (pin "5") (pinfunction "PH0_5") (pintype "bidirectional"))
    )
    (net (code "33") (name "Net-(U$4-PH1)") (class "Default")
      (node (ref "16MHZ") (pin "2") (pinfunction "2_2") (pintype "passive"))
      (node (ref "C10") (pin "1") (pinfunction "1_1") (pintype "passive"))
      (node (ref "U$4") (pin "6") (pinfunction "PH1_6") (pintype "bidirectional"))
    )
    (net (code "34") (name "Net-(U$4-VCAP1)") (class "Default")
      (node (ref "C3") (pin "1") (pinfunction "1_1") (pintype "passive"))
      (node (ref "U$4") (pin "31") (pinfunction "VCAP1_31") (pintype "bidirectional"))
    )
    (net (code "35") (name "Net-(U$4-VCAP2)") (class "Default")
      (node (ref "C8") (pin "1") (pinfunction "1_1") (pintype "passive"))
      (node (ref "U$4") (pin "47") (pinfunction "VCAP2_47") (pintype "bidirectional"))
    )
    (net (code "36") (name "Net-(U1-1V2O)") (class "Default")
      (node (ref "C14") (pin "1") (pinfunction "1_1") (pintype "passive"))
      (node (ref "U1") (pin "22") (pinfunction "1V2O_22") (pintype "output"))
    )
    (net (code "37") (name "Net-(U1-ACTLED)") (class "Default")
      (node (ref "R23") (pin "2") (pinfunction "2_2") (pintype "passive"))
      (node (ref "U1") (pin "27") (pinfunction "ACTLED_27") (pintype "output"))
    )
    (net (code "38") (name "Net-(U1-EXRES1)") (class "Default")
      (node (ref "R19") (pin "2") (pinfunction "2_2") (pintype "passive"))
      (node (ref "U1") (pin "10") (pinfunction "EXRES1_10") (pintype "bidirectional"))
    )
    (net (code "39") (name "Net-(U1-LINKLED)") (class "Default")
      (node (ref "R24") (pin "2") (pinfunction "2_2") (pintype "passive"))
      (node (ref "U1") (pin "25") (pinfunction "LINKLED_25") (pintype "output"))
    )
    (net (code "40") (name "Net-(U1-TOCAP)") (class "Default")
      (node (ref "C13") (pin "1") (pinfunction "1_1") (pintype "passive"))
      (node (ref "U1") (pin "20") (pinfunction "TOCAP_20") (pintype "output"))
    )
    (net (code "41") (name "Net-(U1-XI)") (class "Default")
      (node (ref "C15") (pin "1") (pinfunction "1_1") (pintype "passive"))
      (node (ref "R22") (pin "1") (pinfunction "1_1") (pintype "passive"))
      (node (ref "U1") (pin "30") (pinfunction "XI_30") (pintype "input"))
      (node (ref "Y1") (pin "2") (pinfunction "2_2") (pintype "passive"))
    )
    (net (code "42") (name "Net-(U1-XO)") (class "Default")
      (node (ref "C16") (pin "1") (pinfunction "1_1") (pintype "passive"))
      (node (ref "R22") (pin "2") (pinfunction "2_2") (pintype "passive"))
      (node (ref "U1") (pin "31") (pinfunction "XO_31") (pintype "output"))
      (node (ref "Y1") (pin "1") (pinfunction "1_1") (pintype "passive"))
    )
    (net (code "43") (name "PLTA_ON{slash}OFF") (class "Default")
      (node (ref "PWR_ON") (pin "P$8") (pinfunction "SPARE8_P$8") (pintype "bidirectional"))
      (node (ref "SWITCH_CONNECTOR") (pin "1") (pinfunction "P_1") (pintype "passive"))
      (node (ref "U$1") (pin "50") (pinfunction "PLTA_ON/OFF_50") (pintype "bidirectional"))
      (node (ref "U$2") (pin "50") (pinfunction "PLTA_ON/OFF_50") (pintype "bidirectional"))
      (node (ref "U$3") (pin "50") (pinfunction "PLTA_ON/OFF_50") (pintype "bidirectional"))
    )
    (net (code "44") (name "PWM_1") (class "Default")
      (node (ref "Q1") (pin "3") (pinfunction "D_3") (pintype "bidirectional"))
      (node (ref "R1") (pin "2") (pinfunction "2_2") (pintype "passive"))
      (node (ref "R26") (pin "2") (pinfunction "2_2") (pintype "passive"))
      (node (ref "U$1") (pin "20") (pinfunction "PWM_1_20") (pintype "bidirectional"))
      (node (ref "U$2") (pin "20") (pinfunction "PWM_1_20") (pintype "bidirectional"))
      (node (ref "U$3") (pin "20") (pinfunction "PWM_1_20") (pintype "bidirectional"))
      (node (ref "U$6") (pin "P$9") (pinfunction "PWM_1_P$9") (pintype "bidirectional"))
    )
    (net (code "45") (name "PWM_2") (class "Default")
      (node (ref "Q5") (pin "3") (pinfunction "D_3") (pintype "bidirectional"))
      (node (ref "R2") (pin "2") (pinfunction "2_2") (pintype "passive"))
      (node (ref "R34") (pin "2") (pinfunction "2_2") (pintype "passive"))
      (node (ref "U$1") (pin "21") (pinfunction "PWM_2_21") (pintype "bidirectional"))
      (node (ref "U$2") (pin "21") (pinfunction "PWM_2_21") (pintype "bidirectional"))
      (node (ref "U$3") (pin "21") (pinfunction "PWM_2_21") (pintype "bidirectional"))
      (node (ref "U$6") (pin "P$8") (pinfunction "PWM_2_P$8") (pintype "bidirectional"))
    )
    (net (code "46") (name "PWM_3") (class "Default")
      (node (ref "Q2") (pin "3") (pinfunction "D_3") (pintype "bidirectional"))
      (node (ref "R28") (pin "2") (pinfunction "2_2") (pintype "passive"))
      (node (ref "R3") (pin "2") (pinfunction "2_2") (pintype "passive"))
      (node (ref "U$1") (pin "22") (pinfunction "PWM_3_22") (pintype "bidirectional"))
      (node (ref "U$2") (pin "22") (pinfunction "PWM_3_22") (pintype "bidirectional"))
      (node (ref "U$3") (pin "22") (pinfunction "PWM_3_22") (pintype "bidirectional"))
      (node (ref "U$6") (pin "P$7") (pinfunction "PWM_3_P$7") (pintype "bidirectional"))
    )
    (net (code "47") (name "PWM_4") (class "Default")
      (node (ref "Q6") (pin "3") (pinfunction "D_3") (pintype "bidirectional"))
      (node (ref "R36") (pin "2") (pinfunction "2_2") (pintype "passive"))
      (node (ref "R4") (pin "2") (pinfunction "2_2") (pintype "passive"))
      (node (ref "U$1") (pin "23") (pinfunction "PWM_4_23") (pintype "bidirectional"))
      (node (ref "U$2") (pin "23") (pinfunction "PWM_4_23") (pintype "bidirectional"))
      (node (ref "U$3") (pin "23") (pinfunction "PWM_4_23") (pintype "bidirectional"))
      (node (ref "U$6") (pin "P$6") (pinfunction "PWM_4_P$6") (pintype "bidirectional"))
    )
    (net (code "48") (name "PWM_5") (class "Default")
      (node (ref "Q3") (pin "3") (pinfunction "D_3") (pintype "bidirectional"))
      (node (ref "R30") (pin "2") (pinfunction "2_2") (pintype "passive"))
      (node (ref "R5") (pin "2") (pinfunction "2_2") (pintype "passive"))
      (node (ref "U$1") (pin "24") (pinfunction "PWM_5_24") (pintype "bidirectional"))
      (node (ref "U$2") (pin "24") (pinfunction "PWM_5_24") (pintype "bidirectional"))
      (node (ref "U$3") (pin "24") (pinfunction "PWM_5_24") (pintype "bidirectional"))
      (node (ref "U$6") (pin "P$5") (pinfunction "PWM_5_P$5") (pintype "bidirectional"))
    )
    (net (code "49") (name "PWM_6") (class "Default")
      (node (ref "Q7") (pin "3") (pinfunction "D_3") (pintype "bidirectional"))
      (node (ref "R38") (pin "2") (pinfunction "2_2") (pintype "passive"))
      (node (ref "R6") (pin "2") (pinfunction "2_2") (pintype "passive"))
      (node (ref "U$1") (pin "25") (pinfunction "PWM_6_25") (pintype "bidirectional"))
      (node (ref "U$2") (pin "25") (pinfunction "PWM_6_25") (pintype "bidirectional"))
      (node (ref "U$3") (pin "25") (pinfunction "PWM_6_25") (pintype "bidirectional"))
      (node (ref "U$6") (pin "P$4") (pinfunction "PWM_6_P$4") (pintype "bidirectional"))
    )
    (net (code "50") (name "PWM_7") (class "Default")
      (node (ref "Q4") (pin "3") (pinfunction "D_3") (pintype "bidirectional"))
      (node (ref "R32") (pin "2") (pinfunction "2_2") (pintype "passive"))
      (node (ref "R7") (pin "2") (pinfunction "2_2") (pintype "passive"))
      (node (ref "U$1") (pin "26") (pinfunction "PWM_7_26") (pintype "bidirectional"))
      (node (ref "U$2") (pin "26") (pinfunction "PWM_7_26") (pintype "bidirectional"))
      (node (ref "U$3") (pin "26") (pinfunction "PWM_7_26") (pintype "bidirectional"))
      (node (ref "U$6") (pin "P$3") (pinfunction "PWM_7_P$3") (pintype "bidirectional"))
    )
    (net (code "51") (name "PWM_8") (class "Default")
      (node (ref "Q8") (pin "3") (pinfunction "D_3") (pintype "bidirectional"))
      (node (ref "R40") (pin "2") (pinfunction "2_2") (pintype "passive"))
      (node (ref "R8") (pin "2") (pinfunction "2_2") (pintype "passive"))
      (node (ref "U$1") (pin "27") (pinfunction "PWM_8_27") (pintype "bidirectional"))
      (node (ref "U$2") (pin "27") (pinfunction "PWM_8_27") (pintype "bidirectional"))
      (node (ref "U$3") (pin "27") (pinfunction "PWM_8_27") (pintype "bidirectional"))
      (node (ref "U$6") (pin "P$2") (pinfunction "PWM_8_P$2") (pintype "bidirectional"))
    )
    (net (code "52") (name "ROBOT_SCL") (class "Default")
      (node (ref "P3") (pin "4") (pinfunction "P_4") (pintype "passive"))
      (node (ref "R18") (pin "2") (pinfunction "2_2") (pintype "passive"))
      (node (ref "U$1") (pin "29") (pinfunction "ROBOT_SCL_29") (pintype "bidirectional"))
      (node (ref "U$2") (pin "29") (pinfunction "ROBOT_SCL_29") (pintype "bidirectional"))
      (node (ref "U$3") (pin "29") (pinfunction "ROBOT_SCL_29") (pintype "bidirectional"))
      (node (ref "U$4") (pin "58") (pinfunction "PB6_58") (pintype "bidirectional"))
      (node (ref "U$8") (pin "P$6") (pinfunction "ROBOT_SCL_P$6") (pintype "bidirectional"))
    )
    (net (code "53") (name "ROBOT_SDA") (class "Default")
      (node (ref "P3") (pin "2") (pinfunction "P_2") (pintype "passive"))
      (node (ref "R17") (pin "2") (pinfunction "2_2") (pintype "passive"))
      (node (ref "U$1") (pin "30") (pinfunction "ROBOT_SDA_30") (pintype "bidirectional"))
      (node (ref "U$2") (pin "30") (pinfunction "ROBOT_SDA_30") (pintype "bidirectional"))
      (node (ref "U$3") (pin "30") (pinfunction "ROBOT_SDA_30") (pintype "bidirectional"))
      (node (ref "U$4") (pin "59") (pinfunction "PB7_59") (pintype "bidirectional"))
      (node (ref "U$8") (pin "P$5") (pinfunction "ROBOT_SDA_P$5") (pintype "bidirectional"))
    )
    (net (code "54") (name "SPARE2") (class "Default")
      (node (ref "U$1") (pin "28") (pinfunction "SPARE2_28") (pintype "bidirectional"))
      (node (ref "U$2") (pin "28") (pinfunction "SPARE2_28") (pintype "bidirectional"))
      (node (ref "U$3") (pin "28") (pinfunction "SPARE2_28") (pintype "bidirectional"))
      (node (ref "U$6") (pin "P$1") (pinfunction "SPARE2_P$1") (pintype "bidirectional"))
    )
    (net (code "55") (name "SPARE3") (class "Default")
      (node (ref "U$1") (pin "33") (pinfunction "SPARE3_33") (pintype "bidirectional"))
      (node (ref "U$2") (pin "33") (pinfunction "SPARE3_33") (pintype "bidirectional"))
      (node (ref "U$3") (pin "33") (pinfunction "SPARE3_33") (pintype "bidirectional"))
      (node (ref "U$8") (pin "P$2") (pinfunction "SPARE3_P$2") (pintype "bidirectional"))
    )
    (net (code "56") (name "SPARE4") (class "Default")
      (node (ref "U$1") (pin "34") (pinfunction "SPARE4_34") (pintype "bidirectional"))
      (node (ref "U$2") (pin "34") (pinfunction "SPARE4_34") (pintype "bidirectional"))
      (node (ref "U$3") (pin "34") (pinfunction "SPARE4_34") (pintype "bidirectional"))
      (node (ref "U$8") (pin "P$1") (pinfunction "SPARE4_P$1") (pintype "bidirectional"))
    )
    (net (code "57") (name "SPARE5") (class "Default")
      (node (ref "SWITCH_CONN") (pin "P$9") (pinfunction "SPARE5_P$9") (pintype "bidirectional"))
      (node (ref "U$1") (pin "35") (pinfunction "SPARE5_35") (pintype "bidirectional"))
      (node (ref "U$2") (pin "35") (pinfunction "SPARE5_35") (pintype "bidirectional"))
      (node (ref "U$3") (pin "35") (pinfunction "SPARE5_35") (pintype "bidirectional"))
    )
    (net (code "58") (name "SPARE6") (class "Default")
      (node (ref "SWITCH_CONN") (pin "P$8") (pinfunction "SPARE6_P$8") (pintype "bidirectional"))
      (node (ref "U$1") (pin "36") (pinfunction "SPARE6_36") (pintype "bidirectional"))
      (node (ref "U$2") (pin "36") (pinfunction "SPARE6_36") (pintype "bidirectional"))
      (node (ref "U$3") (pin "36") (pinfunction "SPARE6_36") (pintype "bidirectional"))
    )
    (net (code "59") (name "SPARE7") (class "Default")
      (node (ref "SWITCH_CONN") (pin "P$1") (pinfunction "SPARE7_P$1") (pintype "bidirectional"))
      (node (ref "U$1") (pin "43") (pinfunction "SPARE7_43") (pintype "bidirectional"))
      (node (ref "U$2") (pin "43") (pinfunction "SPARE7_43") (pintype "bidirectional"))
      (node (ref "U$3") (pin "43") (pinfunction "SPARE7_43") (pintype "bidirectional"))
    )
    (net (code "60") (name "SPI_CLK") (class "Default")
      (node (ref "U$4") (pin "21") (pinfunction "PA5/SPI1_SCK_21") (pintype "bidirectional"))
      (node (ref "U1") (pin "33") (pinfunction "SCLK_33") (pintype "input"))
    )
    (net (code "61") (name "SPI_MISO") (class "Default")
      (node (ref "U$4") (pin "22") (pinfunction "PA6/SPI1_MISO_22") (pintype "bidirectional"))
      (node (ref "U1") (pin "34") (pinfunction "MISO_34") (pintype "output"))
    )
    (net (code "62") (name "SPI_MOSI") (class "Default")
      (node (ref "U$4") (pin "23") (pinfunction "PA7/SPI1_MOSI_23") (pintype "bidirectional"))
      (node (ref "U1") (pin "35") (pinfunction "MOSI_35") (pintype "input"))
    )
    (net (code "63") (name "SPI_SS") (class "Default")
      (node (ref "U1") (pin "32") (pinfunction "~{SCSN}_32") (pintype "input"))
    )
    (net (code "64") (name "SWITCH_1") (class "Default")
      (node (ref "R10") (pin "2") (pinfunction "2_2") (pintype "passive"))
      (node (ref "SWITCH_CONN") (pin "P$6") (pinfunction "SWITCH_1_P$6") (pintype "bidirectional"))
      (node (ref "SWITCH_CONNECTOR") (pin "3") (pinfunction "P_3") (pintype "passive"))
      (node (ref "U$1") (pin "38") (pinfunction "SWITCH_1_38") (pintype "output"))
      (node (ref "U$2") (pin "38") (pinfunction "SWITCH_1_38") (pintype "output"))
      (node (ref "U$3") (pin "38") (pinfunction "SWITCH_1_38") (pintype "output"))
    )
    (net (code "65") (name "SWITCH_2") (class "Default")
      (node (ref "R11") (pin "2") (pinfunction "2_2") (pintype "passive"))
      (node (ref "SWITCH_CONN") (pin "P$5") (pinfunction "SWITCH_2_P$5") (pintype "bidirectional"))
      (node (ref "SWITCH_CONNECTOR") (pin "4") (pinfunction "P_4") (pintype "passive"))
      (node (ref "U$1") (pin "39") (pinfunction "SWITCH_2_39") (pintype "output"))
      (node (ref "U$2") (pin "39") (pinfunction "SWITCH_2_39") (pintype "output"))
      (node (ref "U$3") (pin "39") (pinfunction "SWITCH_2_39") (pintype "output"))
    )
    (net (code "66") (name "SWITCH_3") (class "Default")
      (node (ref "R12") (pin "2") (pinfunction "2_2") (pintype "passive"))
      (node (ref "SWITCH_CONN") (pin "P$4") (pinfunction "SWITCH_3_P$4") (pintype "bidirectional"))
      (node (ref "SWITCH_CONNECTOR") (pin "6") (pinfunction "P_6") (pintype "passive"))
      (node (ref "U$1") (pin "40") (pinfunction "SWITCH_3_40") (pintype "output"))
      (node (ref "U$2") (pin "40") (pinfunction "SWITCH_3_40") (pintype "output"))
      (node (ref "U$3") (pin "40") (pinfunction "SWITCH_3_40") (pintype "output"))
    )
    (net (code "67") (name "SWITCH_4") (class "Default")
      (node (ref "R13") (pin "2") (pinfunction "2_2") (pintype "passive"))
      (node (ref "SWITCH_CONN") (pin "P$3") (pinfunction "SWITCH_4_P$3") (pintype "bidirectional"))
      (node (ref "SWITCH_CONNECTOR") (pin "7") (pinfunction "P_7") (pintype "passive"))
      (node (ref "U$1") (pin "41") (pinfunction "SWITCH_4_41") (pintype "output"))
      (node (ref "U$2") (pin "41") (pinfunction "SWITCH_4_41") (pintype "output"))
      (node (ref "U$3") (pin "41") (pinfunction "SWITCH_4_41") (pintype "output"))
    )
    (net (code "68") (name "SWITCH_5") (class "Default")
      (node (ref "R14") (pin "2") (pinfunction "2_2") (pintype "passive"))
      (node (ref "SWITCH_CONN") (pin "P$2") (pinfunction "SWITCH_5_P$2") (pintype "bidirectional"))
      (node (ref "SWITCH_CONNECTOR") (pin "8") (pinfunction "P_8") (pintype "passive"))
      (node (ref "U$1") (pin "42") (pinfunction "SWITCH_5_42") (pintype "output"))
      (node (ref "U$2") (pin "42") (pinfunction "SWITCH_5_42") (pintype "output"))
      (node (ref "U$3") (pin "42") (pinfunction "SWITCH_5_42") (pintype "output"))
    )
    (net (code "69") (name "VBUS") (class "Default")
      (node (ref "D5") (pin "A") (pinfunction "A_A") (pintype "passive"))
      (node (ref "J1") (pin "VBUS") (pinfunction "VBUS_VBUS") (pintype "power_in"))
    )
    (net (code "70") (name "VBUS_3.3") (class "Default")
      (node (ref "R20") (pin "2") (pinfunction "2_2") (pintype "passive"))
      (node (ref "R21") (pin "1") (pinfunction "1_1") (pintype "passive"))
      (node (ref "U$4") (pin "42") (pinfunction "PA9/UART1_TX_42") (pintype "bidirectional"))
    )
    (net (code "71") (name "unconnected-(J1-PadID)") (class "Default")
      (node (ref "J1") (pin "ID") (pinfunction "ID_ID") (pintype "bidirectional"))
    )
    (net (code "72") (name "unconnected-(P2-CT-PadR3)") (class "Default")
      (node (ref "P2") (pin "R3") (pinfunction "CT_R3") (pintype "input"))
    )
    (net (code "73") (name "unconnected-(P2-PadR4)") (class "Default")
      (node (ref "P2") (pin "R4") (pinfunction "R4_R4") (pintype "input"))
    )
    (net (code "74") (name "unconnected-(P2-PadR5)") (class "Default")
      (node (ref "P2") (pin "R5") (pinfunction "R5_R5") (pintype "input"))
    )
    (net (code "75") (name "unconnected-(P2-PadR6)") (class "Default")
      (node (ref "P2") (pin "R6") (pinfunction "R6_R6") (pintype "input"))
    )
    (net (code "76") (name "unconnected-(P2-RD+-PadR7)") (class "Default")
      (node (ref "P2") (pin "R7") (pinfunction "RD+_R7") (pintype "input"))
    )
    (net (code "77") (name "unconnected-(P2-RD--PadR8)") (class "Default")
      (node (ref "P2") (pin "R8") (pinfunction "RD-_R8") (pintype "input"))
    )
    (net (code "78") (name "unconnected-(P2-TD+-PadR1)") (class "Default")
      (node (ref "P2") (pin "R1") (pinfunction "TD+_R1") (pintype "input"))
    )
    (net (code "79") (name "unconnected-(P2-TD--PadR2)") (class "Default")
      (node (ref "P2") (pin "R2") (pinfunction "TD-_R2") (pintype "input"))
    )
    (net (code "80") (name "unconnected-(U$4-BOOT0-Pad60)") (class "Default")
      (node (ref "U$4") (pin "60") (pinfunction "BOOT0_60") (pintype "bidirectional"))
    )
    (net (code "81") (name "unconnected-(U$4-NRST-Pad7)") (class "Default")
      (node (ref "U$4") (pin "7") (pinfunction "NRST_7") (pintype "bidirectional"))
    )
    (net (code "82") (name "unconnected-(U$4-PA0-Pad14)") (class "Default")
      (node (ref "U$4") (pin "14") (pinfunction "PA0_14") (pintype "bidirectional"))
    )
    (net (code "83") (name "unconnected-(U$4-PA1-Pad15)") (class "Default")
      (node (ref "U$4") (pin "15") (pinfunction "PA1_15") (pintype "bidirectional"))
    )
    (net (code "84") (name "unconnected-(U$4-PA2{slash}UART2_TX-Pad16)") (class "Default")
      (node (ref "U$4") (pin "16") (pinfunction "PA2/UART2_TX_16") (pintype "bidirectional"))
    )
    (net (code "85") (name "unconnected-(U$4-PA3{slash}UART2_RX-Pad17)") (class "Default")
      (node (ref "U$4") (pin "17") (pinfunction "PA3/UART2_RX_17") (pintype "bidirectional"))
    )
    (net (code "86") (name "unconnected-(U$4-PA4{slash}SPI1_NSS-Pad20)") (class "Default")
      (node (ref "U$4") (pin "20") (pinfunction "PA4/SPI1_NSS_20") (pintype "bidirectional"))
    )
    (net (code "87") (name "unconnected-(U$4-PA8-Pad41)") (class "Default")
      (node (ref "U$4") (pin "41") (pinfunction "PA8_41") (pintype "bidirectional"))
    )
    (net (code "88") (name "unconnected-(U$4-PA10{slash}UART1_RX-Pad43)") (class "Default")
      (node (ref "U$4") (pin "43") (pinfunction "PA10/UART1_RX_43") (pintype "bidirectional"))
    )
    (net (code "89") (name "unconnected-(U$4-PA13{slash}JTMS-Pad46)") (class "Default")
      (node (ref "U$4") (pin "46") (pinfunction "PA13/JTMS_46") (pintype "bidirectional"))
    )
    (net (code "90") (name "unconnected-(U$4-PA14{slash}JTCK-Pad49)") (class "Default")
      (node (ref "U$4") (pin "49") (pinfunction "PA14/JTCK_49") (pintype "bidirectional"))
    )
    (net (code "91") (name "unconnected-(U$4-PA15{slash}JTDI-Pad50)") (class "Default")
      (node (ref "U$4") (pin "50") (pinfunction "PA15/JTDI_50") (pintype "bidirectional"))
    )
    (net (code "92") (name "unconnected-(U$4-PB0-Pad26)") (class "Default")
      (node (ref "U$4") (pin "26") (pinfunction "PB0_26") (pintype "bidirectional"))
    )
    (net (code "93") (name "unconnected-(U$4-PB1-Pad27)") (class "Default")
      (node (ref "U$4") (pin "27") (pinfunction "PB1_27") (pintype "bidirectional"))
    )
    (net (code "94") (name "unconnected-(U$4-PB2-BOOT1-Pad28)") (class "Default")
      (node (ref "U$4") (pin "28") (pinfunction "PB2-BOOT1_28") (pintype "bidirectional"))
    )
    (net (code "95") (name "unconnected-(U$4-PB3{slash}JTDO-Pad55)") (class "Default")
      (node (ref "U$4") (pin "55") (pinfunction "PB3/JTDO_55") (pintype "bidirectional"))
    )
    (net (code "96") (name "unconnected-(U$4-PB4{slash}JTRST-Pad56)") (class "Default")
      (node (ref "U$4") (pin "56") (pinfunction "PB4/JTRST_56") (pintype "bidirectional"))
    )
    (net (code "97") (name "unconnected-(U$4-PB5-Pad57)") (class "Default")
      (node (ref "U$4") (pin "57") (pinfunction "PB5_57") (pintype "bidirectional"))
    )
    (net (code "98") (name "unconnected-(U$4-PB8-Pad61)") (class "Default")
      (node (ref "U$4") (pin "61") (pinfunction "PB8_61") (pintype "bidirectional"))
    )
    (net (code "99") (name "unconnected-(U$4-PB9-Pad62)") (class "Default")
      (node (ref "U$4") (pin "62") (pinfunction "PB9_62") (pintype "bidirectional"))
    )
    (net (code "100") (name "unconnected-(U$4-PB12{slash}I2S2_WS-Pad33)") (class "Default")
      (node (ref "U$4") (pin "33") (pinfunction "PB12/I2S2_WS_33") (pintype "bidirectional"))
    )
    (net (code "101") (name "unconnected-(U$4-PB13{slash}I2S2_CK-Pad34)") (class "Default")
      (node (ref "U$4") (pin "34") (pinfunction "PB13/I2S2_CK_34") (pintype "bidirectional"))
    )
    (net (code "102") (name "unconnected-(U$4-PB14{slash}I2S2_XD-Pad35)") (class "Default")
      (node (ref "U$4") (pin "35") (pinfunction "PB14/I2S2_XD_35") (pintype "bidirectional"))
    )
    (net (code "103") (name "unconnected-(U$4-PB15{slash}I2S2_SD-Pad36)") (class "Default")
      (node (ref "U$4") (pin "36") (pinfunction "PB15/I2S2_SD_36") (pintype "bidirectional"))
    )
    (net (code "104") (name "unconnected-(U$4-PC0-Pad8)") (class "Default")
      (node (ref "U$4") (pin "8") (pinfunction "PC0_8") (pintype "bidirectional"))
    )
    (net (code "105") (name "unconnected-(U$4-PC1-Pad9)") (class "Default")
      (node (ref "U$4") (pin "9") (pinfunction "PC1_9") (pintype "bidirectional"))
    )
    (net (code "106") (name "unconnected-(U$4-PC2-Pad10)") (class "Default")
      (node (ref "U$4") (pin "10") (pinfunction "PC2_10") (pintype "bidirectional"))
    )
    (net (code "107") (name "unconnected-(U$4-PC3-Pad11)") (class "Default")
      (node (ref "U$4") (pin "11") (pinfunction "PC3_11") (pintype "bidirectional"))
    )
    (net (code "108") (name "unconnected-(U$4-PC4-Pad24)") (class "Default")
      (node (ref "U$4") (pin "24") (pinfunction "PC4_24") (pintype "bidirectional"))
    )
    (net (code "109") (name "unconnected-(U$4-PC5-Pad25)") (class "Default")
      (node (ref "U$4") (pin "25") (pinfunction "PC5_25") (pintype "bidirectional"))
    )
    (net (code "110") (name "unconnected-(U$4-PC6{slash}I2S2_MCK-Pad37)") (class "Default")
      (node (ref "U$4") (pin "37") (pinfunction "PC6/I2S2_MCK_37") (pintype "bidirectional"))
    )
    (net (code "111") (name "unconnected-(U$4-PC7-Pad38)") (class "Default")
      (node (ref "U$4") (pin "38") (pinfunction "PC7_38") (pintype "bidirectional"))
    )
    (net (code "112") (name "unconnected-(U$4-PC8{slash}SDIO_D0-Pad39)") (class "Default")
      (node (ref "U$4") (pin "39") (pinfunction "PC8/SDIO_D0_39") (pintype "bidirectional"))
    )
    (net (code "113") (name "unconnected-(U$4-PC9{slash}SDIO_D1-Pad40)") (class "Default")
      (node (ref "U$4") (pin "40") (pinfunction "PC9/SDIO_D1_40") (pintype "bidirectional"))
    )
    (net (code "114") (name "unconnected-(U$4-PC10{slash}SDIO_D2-Pad51)") (class "Default")
      (node (ref "U$4") (pin "51") (pinfunction "PC10/SDIO_D2_51") (pintype "bidirectional"))
    )
    (net (code "115") (name "unconnected-(U$4-PC11{slash}SDIO_D3-Pad52)") (class "Default")
      (node (ref "U$4") (pin "52") (pinfunction "PC11/SDIO_D3_52") (pintype "bidirectional"))
    )
    (net (code "116") (name "unconnected-(U$4-PC12{slash}SDIO_CLK-Pad53)") (class "Default")
      (node (ref "U$4") (pin "53") (pinfunction "PC12/SDIO_CLK_53") (pintype "bidirectional"))
    )
    (net (code "117") (name "unconnected-(U$4-PC13-Pad2)") (class "Default")
      (node (ref "U$4") (pin "2") (pinfunction "PC13_2") (pintype "bidirectional"))
    )
    (net (code "118") (name "unconnected-(U$4-PD2{slash}SDIO_CMD-Pad54)") (class "Default")
      (node (ref "U$4") (pin "54") (pinfunction "PD2/SDIO_CMD_54") (pintype "bidirectional"))
    )
    (net (code "119") (name "unconnected-(U$4-VBAT-Pad1)") (class "Default")
      (node (ref "U$4") (pin "1") (pinfunction "VBAT_1") (pintype "bidirectional"))
    )
    (net (code "120") (name "unconnected-(U1-DNC-Pad7)") (class "Default")
      (node (ref "U1") (pin "7") (pinfunction "DNC_7") (pintype "bidirectional"))
    )
    (net (code "121") (name "unconnected-(U1-DUPLED-Pad26)") (class "Default")
      (node (ref "U1") (pin "26") (pinfunction "DUPLED_26") (pintype "output"))
    )
    (net (code "122") (name "unconnected-(U1-PMODE0-Pad45)") (class "Default")
      (node (ref "U1") (pin "45") (pinfunction "PMODE0_45") (pintype "input"))
    )
    (net (code "123") (name "unconnected-(U1-PMODE1-Pad44)") (class "Default")
      (node (ref "U1") (pin "44") (pinfunction "PMODE1_44") (pintype "input"))
    )
    (net (code "124") (name "unconnected-(U1-PMODE2-Pad43)") (class "Default")
      (node (ref "U1") (pin "43") (pinfunction "PMODE2_43") (pintype "input"))
    )
    (net (code "125") (name "unconnected-(U1-RSVD2-Pad38)") (class "Default")
      (node (ref "U1") (pin "38") (pinfunction "RSVD2_38") (pintype "input"))
    )
    (net (code "126") (name "unconnected-(U1-RSVD3-Pad39)") (class "Default")
      (node (ref "U1") (pin "39") (pinfunction "RSVD3_39") (pintype "input"))
    )
    (net (code "127") (name "unconnected-(U1-RSVD4-Pad40)") (class "Default")
      (node (ref "U1") (pin "40") (pinfunction "RSVD4_40") (pintype "input"))
    )
    (net (code "128") (name "unconnected-(U1-RSVD5-Pad41)") (class "Default")
      (node (ref "U1") (pin "41") (pinfunction "RSVD5_41") (pintype "input"))
    )
    (net (code "129") (name "unconnected-(U1-RSVD6-Pad42)") (class "Default")
      (node (ref "U1") (pin "42") (pinfunction "RSVD6_42") (pintype "input"))
    )
    (net (code "130") (name "unconnected-(U1-RXN-Pad5)") (class "Default")
      (node (ref "U1") (pin "5") (pinfunction "RXN_5") (pintype "input"))
    )
    (net (code "131") (name "unconnected-(U1-RXP-Pad6)") (class "Default")
      (node (ref "U1") (pin "6") (pinfunction "RXP_6") (pintype "input"))
    )
    (net (code "132") (name "unconnected-(U1-SPDLED-Pad24)") (class "Default")
      (node (ref "U1") (pin "24") (pinfunction "SPDLED_24") (pintype "output"))
    )
    (net (code "133") (name "unconnected-(U1-TXN-Pad1)") (class "Default")
      (node (ref "U1") (pin "1") (pinfunction "TXN_1") (pintype "output"))
    )
    (net (code "134") (name "unconnected-(U1-TXP-Pad2)") (class "Default")
      (node (ref "U1") (pin "2") (pinfunction "TXP_2") (pintype "output"))
    )
    (net (code "135") (name "unconnected-(U1-VBG-Pad18)") (class "Default")
      (node (ref "U1") (pin "18") (pinfunction "VBG_18") (pintype "output"))
    )
  )
)
